# ADC.net
KiCad netlist of a schematic drawn in Altium Designer
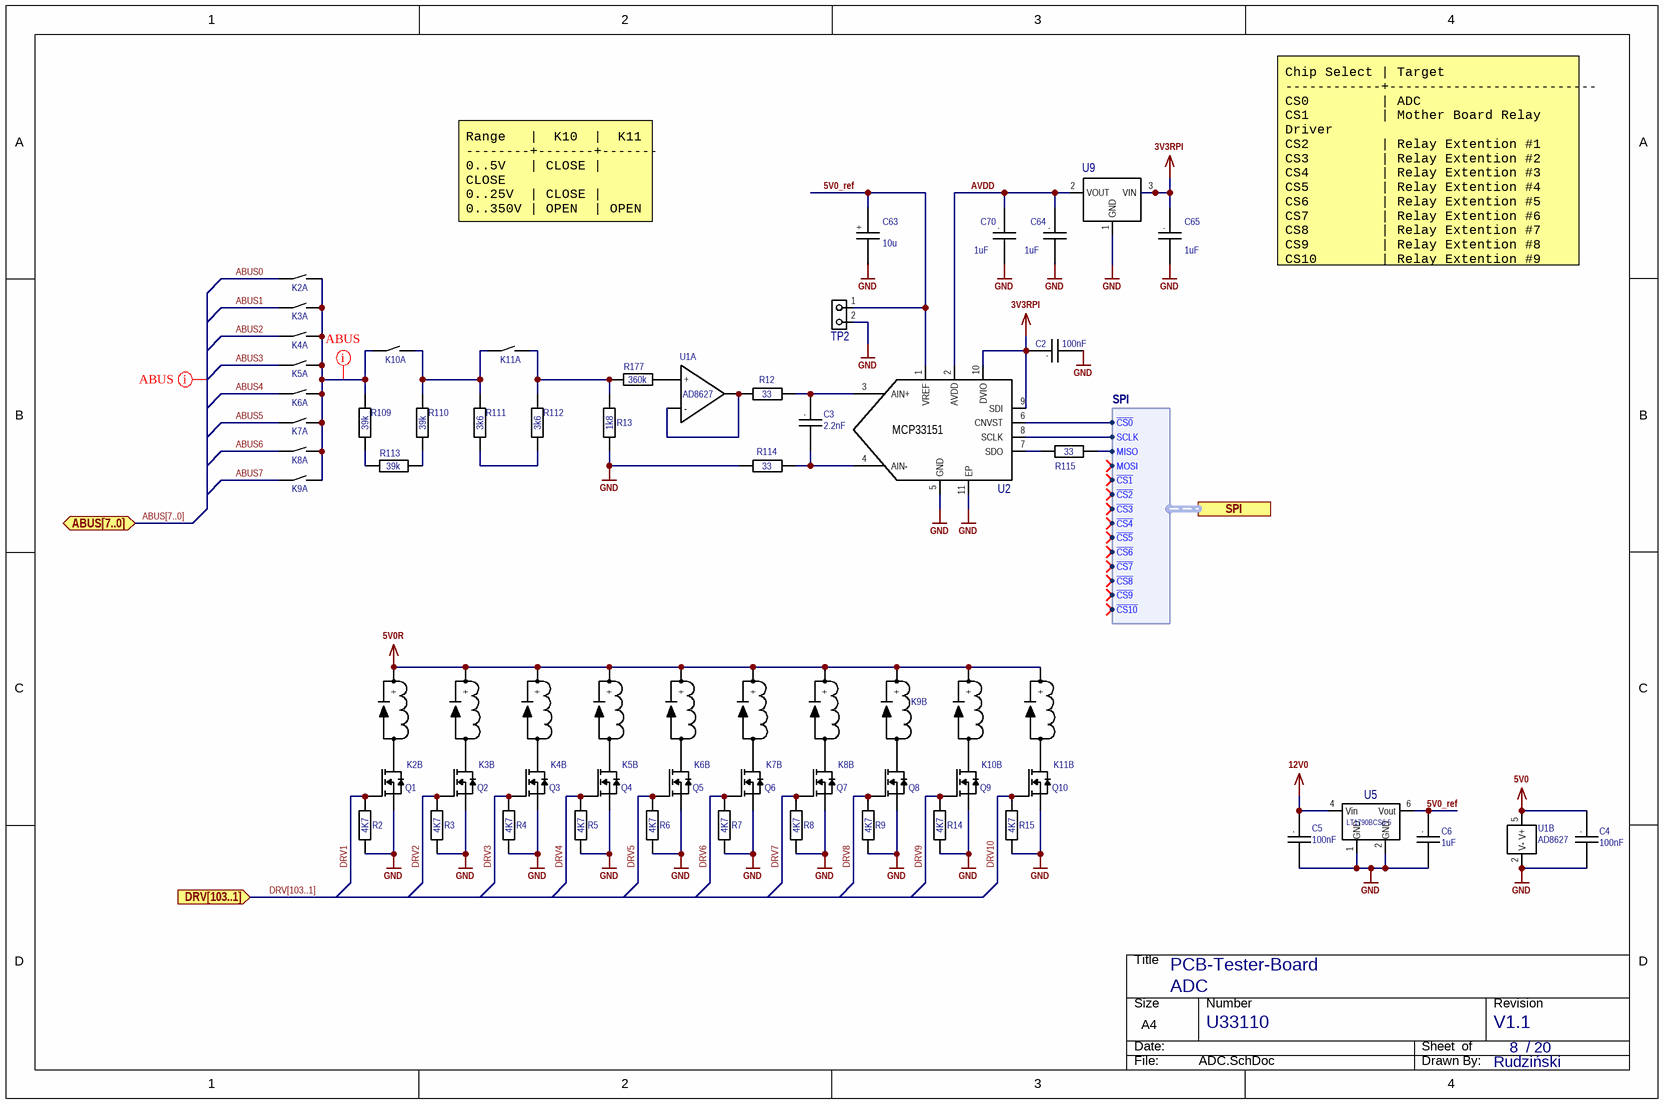
[diagram p0: ADC.SchDoc]

(export (version "E")
  (design (tool "Eeschema 10.0.6"))
  (components
    (comp (ref "C2")
      (value "100nF")
      (footprint "C0402 Reflow")
      (description "CAP CER 0.1UF 25V X7R 0402")
      (fields
        (field (name "TOLERANCE") "±5%")
        (field (name "02. DISTRIBUTOR PART NUMBER") "311-2077-6-ND")
        (field (name "13. CREATED DATE/NAME") "AUG2018/Hören")
      )
      (libsource (lib "chickenfood") (part "C"))
    )
    (comp (ref "C3")
      (value "2.2nF")
      (footprint "C0603 Reflow")
      (description "CAP CER 2200PF 50V X7R 0402")
      (fields
        (field (name "TOLERANCE") "±5%")
        (field (name "02. DISTRIBUTOR PART NUMBER") "1276-1532-6-ND")
        (field (name "13. CREATED DATE/NAME") "AUG2018/Hören")
      )
      (libsource (lib "chickenfood") (part "C"))
    )
    (comp (ref "C4")
      (value "100nF")
      (footprint "C0402 Reflow")
      (description "CAP CER 0.1UF 25V X7R 0402")
      (fields
        (field (name "TOLERANCE") "±5%")
        (field (name "02. DISTRIBUTOR PART NUMBER") "311-2077-6-ND")
        (field (name "13. CREATED DATE/NAME") "AUG2018/Hören")
      )
      (libsource (lib "chickenfood") (part "C"))
    )
    (comp (ref "C5")
      (value "100nF")
      (footprint "C0402 Reflow")
      (description "CAP CER 0.1UF 25V X7R 0402")
      (fields
        (field (name "TOLERANCE") "±5%")
        (field (name "02. DISTRIBUTOR PART NUMBER") "311-2077-6-ND")
        (field (name "13. CREATED DATE/NAME") "AUG2018/Hören")
      )
      (libsource (lib "chickenfood") (part "C"))
    )
    (comp (ref "C6")
      (value "1uF")
      (footprint "C0402 Reflow")
      (description "CAP CER 1UF 6.3V X7R 0402")
      (fields
        (field (name "TOLERANCE") "±10%")
        (field (name "02. DISTRIBUTOR PART NUMBER") "490-13339-6-ND")
        (field (name "13. CREATED DATE/NAME") "AUG2018/Hören")
      )
      (libsource (lib "chickenfood") (part "C"))
    )
    (comp (ref "C63")
      (value "10u")
      (footprint "CAP_TAN_B")
      (description "CAP TANT 10UF 20% 16V 1411")
      (fields
        (field (name "02. DISTRIBUTOR PART NUMBER") "718-2344-1-ND")
        (field (name "07. MANUFACTURER  PART NUMBER") "TMCHB1C106MTRF")
      )
      (libsource (lib "PCB-Tester-Board-V1") (part "C+_TAN"))
    )
    (comp (ref "C64")
      (value "1uF")
      (footprint "C0402 Reflow")
      (description "CAP CER 1UF 6.3V X7R 0402")
      (fields
        (field (name "TOLERANCE") "±10%")
        (field (name "02. DISTRIBUTOR PART NUMBER") "490-13339-6-ND")
        (field (name "13. CREATED DATE/NAME") "AUG2018/Hören")
      )
      (libsource (lib "chickenfood") (part "C"))
    )
    (comp (ref "C65")
      (value "1uF")
      (footprint "C0402 Reflow")
      (description "CAP CER 1UF 6.3V X7R 0402")
      (fields
        (field (name "TOLERANCE") "±10%")
        (field (name "02. DISTRIBUTOR PART NUMBER") "490-13339-6-ND")
        (field (name "13. CREATED DATE/NAME") "AUG2018/Hören")
      )
      (libsource (lib "chickenfood") (part "C"))
    )
    (comp (ref "C70")
      (value "1uF")
      (footprint "C0402 Reflow")
      (description "CAP CER 1UF 6.3V X7R 0402")
      (fields
        (field (name "TOLERANCE") "±10%")
        (field (name "02. DISTRIBUTOR PART NUMBER") "490-13339-6-ND")
        (field (name "13. CREATED DATE/NAME") "AUG2018/Hören")
      )
      (libsource (lib "chickenfood") (part "C"))
    )
    (comp (ref "K2")
      (value "K")
      (footprint "118-1A")
      (description "5V Signal Relais, Normal Open")
      (fields
        (field (name "02. DISTRIBUTOR PART NUMBER") "118-1-A-5/2D")
        (field (name "13. CREATED DATE/NAME") "20.12.17 S. Kaiser")
      )
      (libsource (lib "") (part "118-1-A-5/2D_1"))
    )
    (comp (ref "K3")
      (value "K")
      (footprint "118-1A")
      (description "5V Signal Relais, Normal Open")
      (fields
        (field (name "02. DISTRIBUTOR PART NUMBER") "118-1-A-5/2D")
        (field (name "13. CREATED DATE/NAME") "20.12.17 S. Kaiser")
      )
      (libsource (lib "") (part "118-1-A-5/2D_1"))
    )
    (comp (ref "K4")
      (value "K")
      (footprint "118-1A")
      (description "5V Signal Relais, Normal Open")
      (fields
        (field (name "02. DISTRIBUTOR PART NUMBER") "118-1-A-5/2D")
        (field (name "13. CREATED DATE/NAME") "20.12.17 S. Kaiser")
      )
      (libsource (lib "") (part "118-1-A-5/2D_1"))
    )
    (comp (ref "K5")
      (value "K")
      (footprint "118-1A")
      (description "5V Signal Relais, Normal Open")
      (fields
        (field (name "02. DISTRIBUTOR PART NUMBER") "118-1-A-5/2D")
        (field (name "13. CREATED DATE/NAME") "20.12.17 S. Kaiser")
      )
      (libsource (lib "") (part "118-1-A-5/2D_1"))
    )
    (comp (ref "K6")
      (value "K")
      (footprint "118-1A")
      (description "5V Signal Relais, Normal Open")
      (fields
        (field (name "02. DISTRIBUTOR PART NUMBER") "118-1-A-5/2D")
        (field (name "13. CREATED DATE/NAME") "20.12.17 S. Kaiser")
      )
      (libsource (lib "") (part "118-1-A-5/2D_1"))
    )
    (comp (ref "K7")
      (value "K")
      (footprint "118-1A")
      (description "5V Signal Relais, Normal Open")
      (fields
        (field (name "02. DISTRIBUTOR PART NUMBER") "118-1-A-5/2D")
        (field (name "13. CREATED DATE/NAME") "20.12.17 S. Kaiser")
      )
      (libsource (lib "chickenfood") (part "118-1-A-5/2D"))
    )
    (comp (ref "K8")
      (value "K")
      (footprint "118-1A")
      (description "5V Signal Relais, Normal Open")
      (fields
        (field (name "02. DISTRIBUTOR PART NUMBER") "118-1-A-5/2D")
        (field (name "13. CREATED DATE/NAME") "20.12.17 S. Kaiser")
      )
      (libsource (lib "chickenfood") (part "118-1-A-5/2D"))
    )
    (comp (ref "K9")
      (value "K")
      (footprint "118-1A")
      (description "5V Signal Relais, Normal Open")
      (fields
        (field (name "02. DISTRIBUTOR PART NUMBER") "118-1-A-5/2D")
        (field (name "13. CREATED DATE/NAME") "20.12.17 S. Kaiser")
      )
      (libsource (lib "") (part "118-1-A-5/2D_1"))
    )
    (comp (ref "K10")
      (value "K")
      (footprint "118-1A")
      (description "5V Signal Relais, Normal Open")
      (fields
        (field (name "02. DISTRIBUTOR PART NUMBER") "118-1-A-5/2D")
        (field (name "13. CREATED DATE/NAME") "20.12.17 S. Kaiser")
      )
      (libsource (lib "chickenfood") (part "118-1-A-5/2D"))
    )
    (comp (ref "K11")
      (value "K")
      (footprint "118-1A")
      (description "5V Signal Relais, Normal Open")
      (fields
        (field (name "02. DISTRIBUTOR PART NUMBER") "118-1-A-5/2D")
        (field (name "13. CREATED DATE/NAME") "20.12.17 S. Kaiser")
      )
      (libsource (lib "") (part "118-1-A-5/2D_1"))
    )
    (comp (ref "Q1")
      (value "Q")
      (footprint "SOT23-3")
      (description "MOSFET N-CH 25V 680MA SOT-23")
      (fields
        (field (name "02. DISTRIBUTOR PART NUMBER") "FDV303NDKR-ND")
        (field (name "07. MANUFACTURER  PART NUMBER") "FDV303N")
        (field (name "13. CREATED DATE/NAME") "AUG 2018 / Hören")
      )
      (libsource (lib "SCT8-Board1") (part "FDV303N"))
    )
    (comp (ref "Q2")
      (value "Q")
      (footprint "SOT23-3")
      (description "MOSFET N-CH 25V 680MA SOT-23")
      (fields
        (field (name "02. DISTRIBUTOR PART NUMBER") "FDV303NDKR-ND")
        (field (name "07. MANUFACTURER  PART NUMBER") "FDV303N")
        (field (name "13. CREATED DATE/NAME") "AUG 2018 / Hören")
      )
      (libsource (lib "SCT8-Board1") (part "FDV303N"))
    )
    (comp (ref "Q3")
      (value "Q")
      (footprint "SOT23-3")
      (description "MOSFET N-CH 25V 680MA SOT-23")
      (fields
        (field (name "02. DISTRIBUTOR PART NUMBER") "FDV303NDKR-ND")
        (field (name "07. MANUFACTURER  PART NUMBER") "FDV303N")
        (field (name "13. CREATED DATE/NAME") "AUG 2018 / Hören")
      )
      (libsource (lib "SCT8-Board1") (part "FDV303N"))
    )
    (comp (ref "Q4")
      (value "Q")
      (footprint "SOT23-3")
      (description "MOSFET N-CH 25V 680MA SOT-23")
      (fields
        (field (name "02. DISTRIBUTOR PART NUMBER") "FDV303NDKR-ND")
        (field (name "07. MANUFACTURER  PART NUMBER") "FDV303N")
        (field (name "13. CREATED DATE/NAME") "AUG 2018 / Hören")
      )
      (libsource (lib "SCT8-Board1") (part "FDV303N"))
    )
    (comp (ref "Q5")
      (value "Q")
      (footprint "SOT23-3")
      (description "MOSFET N-CH 25V 680MA SOT-23")
      (fields
        (field (name "02. DISTRIBUTOR PART NUMBER") "FDV303NDKR-ND")
        (field (name "07. MANUFACTURER  PART NUMBER") "FDV303N")
        (field (name "13. CREATED DATE/NAME") "AUG 2018 / Hören")
      )
      (libsource (lib "SCT8-Board1") (part "FDV303N"))
    )
    (comp (ref "Q6")
      (value "Q")
      (footprint "SOT23-3")
      (description "MOSFET N-CH 25V 680MA SOT-23")
      (fields
        (field (name "02. DISTRIBUTOR PART NUMBER") "FDV303NDKR-ND")
        (field (name "07. MANUFACTURER  PART NUMBER") "FDV303N")
        (field (name "13. CREATED DATE/NAME") "AUG 2018 / Hören")
      )
      (libsource (lib "SCT8-Board1") (part "FDV303N"))
    )
    (comp (ref "Q7")
      (value "Q")
      (footprint "SOT23-3")
      (description "MOSFET N-CH 25V 680MA SOT-23")
      (fields
        (field (name "02. DISTRIBUTOR PART NUMBER") "FDV303NDKR-ND")
        (field (name "07. MANUFACTURER  PART NUMBER") "FDV303N")
        (field (name "13. CREATED DATE/NAME") "AUG 2018 / Hören")
      )
      (libsource (lib "SCT8-Board1") (part "FDV303N"))
    )
    (comp (ref "Q8")
      (value "Q")
      (footprint "SOT23-3")
      (description "MOSFET N-CH 25V 680MA SOT-23")
      (fields
        (field (name "02. DISTRIBUTOR PART NUMBER") "FDV303NDKR-ND")
        (field (name "07. MANUFACTURER  PART NUMBER") "FDV303N")
        (field (name "13. CREATED DATE/NAME") "AUG 2018 / Hören")
      )
      (libsource (lib "SCT8-Board1") (part "FDV303N"))
    )
    (comp (ref "Q9")
      (value "Q")
      (footprint "SOT23-3")
      (description "MOSFET N-CH 25V 680MA SOT-23")
      (fields
        (field (name "02. DISTRIBUTOR PART NUMBER") "FDV303NDKR-ND")
        (field (name "07. MANUFACTURER  PART NUMBER") "FDV303N")
        (field (name "13. CREATED DATE/NAME") "AUG 2018 / Hören")
      )
      (libsource (lib "SCT8-Board1") (part "FDV303N"))
    )
    (comp (ref "Q10")
      (value "Q")
      (footprint "SOT23-3")
      (description "MOSFET N-CH 25V 680MA SOT-23")
      (fields
        (field (name "02. DISTRIBUTOR PART NUMBER") "FDV303NDKR-ND")
        (field (name "07. MANUFACTURER  PART NUMBER") "FDV303N")
        (field (name "13. CREATED DATE/NAME") "AUG 2018 / Hören")
      )
      (libsource (lib "SCT8-Board1") (part "FDV303N"))
    )
    (comp (ref "R2")
      (value "4K7")
      (footprint "R0603 Reflow")
      (description "RES SMD 4.7K OHM 1% 1/10W 0603")
      (fields
        (field (name "TOLERANCE") "±1%")
        (field (name "02. DISTRIBUTOR PART NUMBER") "311-4.70KHRCT-ND")
        (field (name "13. CREATED DATE/NAME") "AUG2018/Hören")
      )
      (libsource (lib "chickenfood") (part "R"))
    )
    (comp (ref "R3")
      (value "4K7")
      (footprint "R0603 Reflow")
      (description "RES SMD 4.7K OHM 1% 1/10W 0603")
      (fields
        (field (name "TOLERANCE") "±1%")
        (field (name "02. DISTRIBUTOR PART NUMBER") "311-4.70KHRCT-ND")
        (field (name "13. CREATED DATE/NAME") "AUG2018/Hören")
      )
      (libsource (lib "chickenfood") (part "R"))
    )
    (comp (ref "R4")
      (value "4K7")
      (footprint "R0603 Reflow")
      (description "RES SMD 4.7K OHM 1% 1/10W 0603")
      (fields
        (field (name "TOLERANCE") "±1%")
        (field (name "02. DISTRIBUTOR PART NUMBER") "311-4.70KHRCT-ND")
        (field (name "13. CREATED DATE/NAME") "AUG2018/Hören")
      )
      (libsource (lib "chickenfood") (part "R"))
    )
    (comp (ref "R5")
      (value "4K7")
      (footprint "R0603 Reflow")
      (description "RES SMD 4.7K OHM 1% 1/10W 0603")
      (fields
        (field (name "TOLERANCE") "±1%")
        (field (name "02. DISTRIBUTOR PART NUMBER") "311-4.70KHRCT-ND")
        (field (name "13. CREATED DATE/NAME") "AUG2018/Hören")
      )
      (libsource (lib "chickenfood") (part "R"))
    )
    (comp (ref "R6")
      (value "4K7")
      (footprint "R0603 Reflow")
      (description "RES SMD 4.7K OHM 1% 1/10W 0603")
      (fields
        (field (name "TOLERANCE") "±1%")
        (field (name "02. DISTRIBUTOR PART NUMBER") "311-4.70KHRCT-ND")
        (field (name "13. CREATED DATE/NAME") "AUG2018/Hören")
      )
      (libsource (lib "chickenfood") (part "R"))
    )
    (comp (ref "R7")
      (value "4K7")
      (footprint "R0603 Reflow")
      (description "RES SMD 4.7K OHM 1% 1/10W 0603")
      (fields
        (field (name "TOLERANCE") "±1%")
        (field (name "02. DISTRIBUTOR PART NUMBER") "311-4.70KHRCT-ND")
        (field (name "13. CREATED DATE/NAME") "AUG2018/Hören")
      )
      (libsource (lib "chickenfood") (part "R"))
    )
    (comp (ref "R8")
      (value "4K7")
      (footprint "R0603 Reflow")
      (description "RES SMD 4.7K OHM 1% 1/10W 0603")
      (fields
        (field (name "TOLERANCE") "±1%")
        (field (name "02. DISTRIBUTOR PART NUMBER") "311-4.70KHRCT-ND")
        (field (name "13. CREATED DATE/NAME") "AUG2018/Hören")
      )
      (libsource (lib "chickenfood") (part "R"))
    )
    (comp (ref "R9")
      (value "4K7")
      (footprint "R0603 Reflow")
      (description "RES SMD 4.7K OHM 1% 1/10W 0603")
      (fields
        (field (name "TOLERANCE") "±1%")
        (field (name "02. DISTRIBUTOR PART NUMBER") "311-4.70KHRCT-ND")
        (field (name "13. CREATED DATE/NAME") "AUG2018/Hören")
      )
      (libsource (lib "chickenfood") (part "R"))
    )
    (comp (ref "R12")
      (value "33")
      (footprint "R0402 Reflow")
      (description "RES SMD 33 OHM 1% 1/16W 0402")
      (fields
        (field (name "TOLERANCE") "±1%")
        (field (name "02. DISTRIBUTOR PART NUMBER") "311-33.0LRDKR-ND")
        (field (name "13. CREATED DATE/NAME") "AUG2018/Hören")
      )
      (libsource (lib "") (part "R_1"))
    )
    (comp (ref "R13")
      (value "1k8")
      (footprint "R0603 Reflow")
      (description "RES SMD 1.8K OHM 1% 1/16W 0402")
      (fields
        (field (name "TOLERANCE") "±1%")
        (field (name "02. DISTRIBUTOR PART NUMBER") "311-1.80KLRCT-ND")
        (field (name "13. CREATED DATE/NAME") "AUG2018/Hören")
      )
      (libsource (lib "chickenfood") (part "R"))
    )
    (comp (ref "R14")
      (value "4K7")
      (footprint "R0603 Reflow")
      (description "RES SMD 4.7K OHM 1% 1/10W 0603")
      (fields
        (field (name "TOLERANCE") "±1%")
        (field (name "02. DISTRIBUTOR PART NUMBER") "311-4.70KHRCT-ND")
        (field (name "13. CREATED DATE/NAME") "AUG2018/Hören")
      )
      (libsource (lib "chickenfood") (part "R"))
    )
    (comp (ref "R15")
      (value "4K7")
      (footprint "R0603 Reflow")
      (description "RES SMD 4.7K OHM 1% 1/10W 0603")
      (fields
        (field (name "TOLERANCE") "±1%")
        (field (name "02. DISTRIBUTOR PART NUMBER") "311-4.70KHRCT-ND")
        (field (name "13. CREATED DATE/NAME") "AUG2018/Hören")
      )
      (libsource (lib "chickenfood") (part "R"))
    )
    (comp (ref "R109")
      (value "39k")
      (footprint "R2512 Reflow")
      (description "CRGP 2512 39K 1%")
      (fields
        (field (name "TOLERANCE") "±1%")
        (field (name "02. DISTRIBUTOR PART NUMBER") "A130740CT-ND")
        (field (name "13. CREATED DATE/NAME") "AUG2018/Hören")
      )
      (libsource (lib "") (part "R_1"))
    )
    (comp (ref "R110")
      (value "39k")
      (footprint "R2512 Reflow")
      (description "CRGP 2512 39K 1%")
      (fields
        (field (name "TOLERANCE") "±1%")
        (field (name "02. DISTRIBUTOR PART NUMBER") "A130740CT-ND")
        (field (name "13. CREATED DATE/NAME") "AUG2018/Hören")
      )
      (libsource (lib "") (part "R_1"))
    )
    (comp (ref "R111")
      (value "3k6")
      (footprint "R0603 Reflow")
      (description "RES SMD 3.6K OHM 1% 1/10W 0603")
      (fields
        (field (name "TOLERANCE") "±1%")
        (field (name "02. DISTRIBUTOR PART NUMBER") "311-3.60KHRCT-ND")
        (field (name "13. CREATED DATE/NAME") "AUG2018/Hören")
      )
      (libsource (lib "") (part "R_1"))
    )
    (comp (ref "R112")
      (value "3k6")
      (footprint "R0603 Reflow")
      (description "RES SMD 3.6K OHM 1% 1/10W 0603")
      (fields
        (field (name "TOLERANCE") "±1%")
        (field (name "02. DISTRIBUTOR PART NUMBER") "311-3.60KHRCT-ND")
        (field (name "13. CREATED DATE/NAME") "AUG2018/Hören")
      )
      (libsource (lib "") (part "R_1"))
    )
    (comp (ref "R113")
      (value "39k")
      (footprint "R2512 Reflow")
      (description "CRGP 2512 39K 1%")
      (fields
        (field (name "TOLERANCE") "±1%")
        (field (name "02. DISTRIBUTOR PART NUMBER") "A130740CT-ND")
        (field (name "13. CREATED DATE/NAME") "AUG2018/Hören")
      )
      (libsource (lib "PCB-Tester-Board-V1") (part "R"))
    )
    (comp (ref "R114")
      (value "33")
      (footprint "R0402 Reflow")
      (description "RES SMD 33 OHM 1% 1/16W 0402")
      (fields
        (field (name "TOLERANCE") "±1%")
        (field (name "02. DISTRIBUTOR PART NUMBER") "311-33.0LRDKR-ND")
        (field (name "13. CREATED DATE/NAME") "AUG2018/Hören")
      )
      (libsource (lib "") (part "R_1"))
    )
    (comp (ref "R115")
      (value "33")
      (footprint "R0402 Reflow")
      (description "RES SMD 33 OHM 1% 1/16W 0402")
      (fields
        (field (name "TOLERANCE") "±1%")
        (field (name "02. DISTRIBUTOR PART NUMBER") "311-33.0LRDKR-ND")
        (field (name "13. CREATED DATE/NAME") "AUG2018/Hören")
      )
      (libsource (lib "PCB-Tester-Board-V1") (part "R_19"))
    )
    (comp (ref "R177")
      (value "360k")
      (footprint "R1206 Reflow")
      (description "RES SMD 360K OHM 1% 1/4W 1206")
      (fields
        (field (name "TOLERANCE") "±1%")
        (field (name "02. DISTRIBUTOR PART NUMBER") "311-360KFRCT-ND")
        (field (name "13. CREATED DATE/NAME") "AUG2018/Hören")
      )
      (libsource (lib "") (part "R_1"))
    )
    (comp (ref "TP2")
      (value "TP")
      (footprint "DualTestpoint 100mils")
      (description "Dual testpoint, pitch 2.54mm")
      (fields
        (field (name "02. DISTRIBUTOR PART NUMBER") "HMTSW-103-07-G-S-240")
        (field (name "13. CREATED DATE/NAME") "AUG2018/Hören")
      )
      (libsource (lib "PCB-Tester-Board-V1") (part "DualTestpoint 100mils"))
    )
    (comp (ref "U1")
      (value "U")
      (footprint "SC70-5")
      (description "IC OPAMP JFET 5MHZ RRO SC70-5")
      (fields
        (field (name "02. DISTRIBUTOR PART NUMBER") "AD8627AKSZ-R2DKR-ND")
        (field (name "07. MANUFACTURER  PART NUMBER") "AD8627AKSZ-R2")
        (field (name "PART") "AD8627")
        (field (name "13. CREATED DATE/NAME") "AUG 2018 / Hören")
      )
      (libsource (lib "PCB-Tester-Board") (part "AD8627"))
    )
    (comp (ref "U2")
      (value "U")
      (footprint "TDFN10EP")
      (description "14-BIT 1 MSPS SGL CH SGL-ENDED S")
      (fields
        (field (name "02. DISTRIBUTOR PART NUMBER") "MCP33151-10T-E/MNDKR-ND")
        (field (name "07. MANUFACTURER  PART NUMBER") "MCP33151-10T-E/MN")
        (field (name "NICNAME") "MCP33151")
        (field (name "13. CREATED DATE/NAME") "AUG 2018 / Hören")
      )
      (libsource (lib "tom") (part "MCP33151-10T-E/MN"))
    )
    (comp (ref "U5")
      (value "U")
      (footprint "TSOT23-6(S6)")
      (description "IC VREF SERIES 5V, 0.1% TSOT-23-6")
      (fields
        (field (name "02. DISTRIBUTOR PART NUMBER") "LT1790BCS6-5#TRMPBFDKR-ND")
        (field (name "07. MANUFACTURER  PART NUMBER") "LT1790BCS6-5#TRMPBF")
        (field (name "NICNAME") "LT1790BCS6-5")
        (field (name "13. CREATED DATE/NAME") "AUG 2018 / Hören")
      )
      (libsource (lib "tom") (part "LT1790BCS6-5"))
    )
    (comp (ref "U9")
      (value "U")
      (footprint "SOT23-3")
      (description "IC REG LINEAR 1.8V 250MA SOT23-3")
      (fields
        (field (name "02. DISTRIBUTOR PART NUMBER") "AP2138N-1.8TRG1DICT-ND")
        (field (name "07. MANUFACTURER  PART NUMBER") "AP2138N-1.8TRG1")
      )
      (libsource (lib "PCB-Tester-Board-V1") (part "AP2138N"))
    )
  )
  (nets
    (net (code "95") (name "/5V0_ref") (class "Default")
      (node (ref "C6") (pin "1") (pinfunction "1_1") (pintype "passive"))
      (node (ref "C63") (pin "1") (pinfunction "1_1") (pintype "passive"))
      (node (ref "TP2") (pin "1") (pinfunction "1_1") (pintype "passive"))
      (node (ref "U2") (pin "1") (pinfunction "VREF_1") (pintype "passive"))
      (node (ref "U5") (pin "6") (pinfunction "Vout_6") (pintype "passive"))
    )
    (net (code "96") (name "/ABUS0") (class "Default")
      (node (ref "K2") (pin "4") (pinfunction "CB_4") (pintype "passive"))
    )
    (net (code "97") (name "/ABUS1") (class "Default")
      (node (ref "K3") (pin "4") (pinfunction "CB_4") (pintype "passive"))
    )
    (net (code "98") (name "/ABUS2") (class "Default")
      (node (ref "K4") (pin "4") (pinfunction "CB_4") (pintype "passive"))
    )
    (net (code "99") (name "/ABUS3") (class "Default")
      (node (ref "K5") (pin "4") (pinfunction "CB_4") (pintype "passive"))
    )
    (net (code "100") (name "/ABUS4") (class "Default")
      (node (ref "K6") (pin "4") (pinfunction "CB_4") (pintype "passive"))
    )
    (net (code "101") (name "/ABUS5") (class "Default")
      (node (ref "K7") (pin "4") (pinfunction "CB_4") (pintype "passive"))
    )
    (net (code "102") (name "/ABUS6") (class "Default")
      (node (ref "K8") (pin "4") (pinfunction "CB_4") (pintype "passive"))
    )
    (net (code "103") (name "/ABUS7") (class "Default")
      (node (ref "K9") (pin "4") (pinfunction "CB_4") (pintype "passive"))
    )
    (net (code "105") (name "/AVDD") (class "Default")
      (node (ref "C64") (pin "1") (pinfunction "1_1") (pintype "passive"))
      (node (ref "C70") (pin "1") (pinfunction "1_1") (pintype "passive"))
      (node (ref "U2") (pin "2") (pinfunction "AVDD_2") (pintype "passive"))
      (node (ref "U9") (pin "2") (pinfunction "VOUT_2") (pintype "passive"))
    )
    (net (code "106") (name "/DRV1") (class "Default")
      (node (ref "Q1") (pin "1") (pinfunction "G_1") (pintype "passive"))
      (node (ref "R2") (pin "2") (pinfunction "2_2") (pintype "passive"))
    )
    (net (code "107") (name "/DRV2") (class "Default")
      (node (ref "Q2") (pin "1") (pinfunction "G_1") (pintype "passive"))
      (node (ref "R3") (pin "2") (pinfunction "2_2") (pintype "passive"))
    )
    (net (code "108") (name "/DRV3") (class "Default")
      (node (ref "Q3") (pin "1") (pinfunction "G_1") (pintype "passive"))
      (node (ref "R4") (pin "2") (pinfunction "2_2") (pintype "passive"))
    )
    (net (code "109") (name "/DRV4") (class "Default")
      (node (ref "Q4") (pin "1") (pinfunction "G_1") (pintype "passive"))
      (node (ref "R5") (pin "2") (pinfunction "2_2") (pintype "passive"))
    )
    (net (code "110") (name "/DRV5") (class "Default")
      (node (ref "Q5") (pin "1") (pinfunction "G_1") (pintype "passive"))
      (node (ref "R6") (pin "2") (pinfunction "2_2") (pintype "passive"))
    )
    (net (code "111") (name "/DRV6") (class "Default")
      (node (ref "Q6") (pin "1") (pinfunction "G_1") (pintype "passive"))
      (node (ref "R7") (pin "2") (pinfunction "2_2") (pintype "passive"))
    )
    (net (code "112") (name "/DRV7") (class "Default")
      (node (ref "Q7") (pin "1") (pinfunction "G_1") (pintype "passive"))
      (node (ref "R8") (pin "2") (pinfunction "2_2") (pintype "passive"))
    )
    (net (code "113") (name "/DRV8") (class "Default")
      (node (ref "Q8") (pin "1") (pinfunction "G_1") (pintype "passive"))
      (node (ref "R9") (pin "2") (pinfunction "2_2") (pintype "passive"))
    )
    (net (code "114") (name "/DRV9") (class "Default")
      (node (ref "Q9") (pin "1") (pinfunction "G_1") (pintype "passive"))
      (node (ref "R14") (pin "2") (pinfunction "2_2") (pintype "passive"))
    )
    (net (code "115") (name "/DRV10") (class "Default")
      (node (ref "Q10") (pin "1") (pinfunction "G_1") (pintype "passive"))
      (node (ref "R15") (pin "2") (pinfunction "2_2") (pintype "passive"))
    )
    (net (code "117") (name "/MISO") (class "Default")
      (node (ref "R115") (pin "2") (pinfunction "2_2") (pintype "passive"))
    )
    (net (code "118") (name "/SCLK") (class "Default")
      (node (ref "U2") (pin "8") (pinfunction "SCLK_8") (pintype "passive"))
    )
    (net (code "120") (name "/~{CS0}") (class "Default")
      (node (ref "U2") (pin "6") (pinfunction "CNVST_6") (pintype "passive"))
    )
    (net (code "121") (name "3V3RPI") (class "Default")
      (node (ref "C2") (pin "1") (pinfunction "1_1") (pintype "passive"))
      (node (ref "C65") (pin "1") (pinfunction "1_1") (pintype "passive"))
      (node (ref "U2") (pin "10") (pinfunction "DVIO_10") (pintype "passive"))
      (node (ref "U2") (pin "9") (pinfunction "SDI_9") (pintype "passive"))
      (node (ref "U9") (pin "3") (pinfunction "VIN_3") (pintype "passive"))
    )
    (net (code "122") (name "5V0") (class "Default")
      (node (ref "C4") (pin "1") (pinfunction "1_1") (pintype "passive"))
      (node (ref "U1") (pin "5") (pinfunction "V+_5") (pintype "passive"))
    )
    (net (code "123") (name "5V0R") (class "Default")
      (node (ref "K10") (pin "1") (pinfunction "+_1") (pintype "passive"))
      (node (ref "K11") (pin "1") (pinfunction "+_1") (pintype "passive"))
      (node (ref "K2") (pin "1") (pinfunction "+_1") (pintype "passive"))
      (node (ref "K3") (pin "1") (pinfunction "+_1") (pintype "passive"))
      (node (ref "K4") (pin "1") (pinfunction "+_1") (pintype "passive"))
      (node (ref "K5") (pin "1") (pinfunction "+_1") (pintype "passive"))
      (node (ref "K6") (pin "1") (pinfunction "+_1") (pintype "passive"))
      (node (ref "K7") (pin "1") (pinfunction "+_1") (pintype "passive"))
      (node (ref "K8") (pin "1") (pinfunction "+_1") (pintype "passive"))
      (node (ref "K9") (pin "1") (pinfunction "+_1") (pintype "passive"))
    )
    (net (code "124") (name "12V0") (class "Default")
      (node (ref "C5") (pin "1") (pinfunction "1_1") (pintype "passive"))
      (node (ref "U5") (pin "4") (pinfunction "Vin_4") (pintype "passive"))
    )
    (net (code "125") (name "GND") (class "Default")
      (node (ref "C2") (pin "2") (pinfunction "2_2") (pintype "passive"))
      (node (ref "C4") (pin "2") (pinfunction "2_2") (pintype "passive"))
      (node (ref "C5") (pin "2") (pinfunction "2_2") (pintype "passive"))
      (node (ref "C6") (pin "2") (pinfunction "2_2") (pintype "passive"))
      (node (ref "C63") (pin "2") (pinfunction "2_2") (pintype "passive"))
      (node (ref "C64") (pin "2") (pinfunction "2_2") (pintype "passive"))
      (node (ref "C65") (pin "2") (pinfunction "2_2") (pintype "passive"))
      (node (ref "C70") (pin "2") (pinfunction "2_2") (pintype "passive"))
      (node (ref "Q1") (pin "2") (pinfunction "S_2") (pintype "passive"))
      (node (ref "Q10") (pin "2") (pinfunction "S_2") (pintype "passive"))
      (node (ref "Q2") (pin "2") (pinfunction "S_2") (pintype "passive"))
      (node (ref "Q3") (pin "2") (pinfunction "S_2") (pintype "passive"))
      (node (ref "Q4") (pin "2") (pinfunction "S_2") (pintype "passive"))
      (node (ref "Q5") (pin "2") (pinfunction "S_2") (pintype "passive"))
      (node (ref "Q6") (pin "2") (pinfunction "S_2") (pintype "passive"))
      (node (ref "Q7") (pin "2") (pinfunction "S_2") (pintype "passive"))
      (node (ref "Q8") (pin "2") (pinfunction "S_2") (pintype "passive"))
      (node (ref "Q9") (pin "2") (pinfunction "S_2") (pintype "passive"))
      (node (ref "R114") (pin "2") (pinfunction "2_2") (pintype "passive"))
      (node (ref "R13") (pin "1") (pinfunction "1_1") (pintype "passive"))
      (node (ref "R14") (pin "1") (pinfunction "1_1") (pintype "passive"))
      (node (ref "R15") (pin "1") (pinfunction "1_1") (pintype "passive"))
      (node (ref "R2") (pin "1") (pinfunction "1_1") (pintype "passive"))
      (node (ref "R3") (pin "1") (pinfunction "1_1") (pintype "passive"))
      (node (ref "R4") (pin "1") (pinfunction "1_1") (pintype "passive"))
      (node (ref "R5") (pin "1") (pinfunction "1_1") (pintype "passive"))
      (node (ref "R6") (pin "1") (pinfunction "1_1") (pintype "passive"))
      (node (ref "R7") (pin "1") (pinfunction "1_1") (pintype "passive"))
      (node (ref "R8") (pin "1") (pinfunction "1_1") (pintype "passive"))
      (node (ref "R9") (pin "1") (pinfunction "1_1") (pintype "passive"))
      (node (ref "TP2") (pin "2") (pinfunction "2_2") (pintype "passive"))
      (node (ref "U1") (pin "2") (pinfunction "V-_2") (pintype "passive"))
      (node (ref "U2") (pin "11") (pinfunction "EP_11") (pintype "passive"))
      (node (ref "U2") (pin "5") (pinfunction "GND_5") (pintype "passive"))
      (node (ref "U5") (pin "1") (pinfunction "GND_1") (pintype "passive"))
      (node (ref "U5") (pin "2") (pinfunction "GND_2") (pintype "passive"))
      (node (ref "U9") (pin "1") (pinfunction "GND_1") (pintype "passive"))
    )
    (net (code "126") (name "Net-(K2B--)") (class "Default")
      (node (ref "K2") (pin "2") (pinfunction "-_2") (pintype "passive"))
      (node (ref "Q1") (pin "3") (pinfunction "D_3") (pintype "passive"))
    )
    (net (code "127") (name "Net-(K3B--)") (class "Default")
      (node (ref "K3") (pin "2") (pinfunction "-_2") (pintype "passive"))
      (node (ref "Q2") (pin "3") (pinfunction "D_3") (pintype "passive"))
    )
    (net (code "128") (name "Net-(K4B--)") (class "Default")
      (node (ref "K4") (pin "2") (pinfunction "-_2") (pintype "passive"))
      (node (ref "Q3") (pin "3") (pinfunction "D_3") (pintype "passive"))
    )
    (net (code "129") (name "Net-(K5B--)") (class "Default")
      (node (ref "K5") (pin "2") (pinfunction "-_2") (pintype "passive"))
      (node (ref "Q4") (pin "3") (pinfunction "D_3") (pintype "passive"))
    )
    (net (code "130") (name "Net-(K6B--)") (class "Default")
      (node (ref "K6") (pin "2") (pinfunction "-_2") (pintype "passive"))
      (node (ref "Q5") (pin "3") (pinfunction "D_3") (pintype "passive"))
    )
    (net (code "131") (name "Net-(K7B--)") (class "Default")
      (node (ref "K7") (pin "2") (pinfunction "-_2") (pintype "passive"))
      (node (ref "Q6") (pin "3") (pinfunction "D_3") (pintype "passive"))
    )
    (net (code "132") (name "Net-(K8B--)") (class "Default")
      (node (ref "K8") (pin "2") (pinfunction "-_2") (pintype "passive"))
      (node (ref "Q7") (pin "3") (pinfunction "D_3") (pintype "passive"))
    )
    (net (code "133") (name "Net-(K9B--)") (class "Default")
      (node (ref "K9") (pin "2") (pinfunction "-_2") (pintype "passive"))
      (node (ref "Q8") (pin "3") (pinfunction "D_3") (pintype "passive"))
    )
    (net (code "134") (name "Net-(K10A-CA)") (class "Default")
      (node (ref "K10") (pin "3") (pinfunction "CA_3") (pintype "passive"))
      (node (ref "K11") (pin "4") (pinfunction "CB_4") (pintype "passive"))
      (node (ref "R110") (pin "2") (pinfunction "2_2") (pintype "passive"))
      (node (ref "R111") (pin "2") (pinfunction "2_2") (pintype "passive"))
    )
    (net (code "135") (name "Net-(K10A-CB)") (class "Default")
      (node (ref "K10") (pin "4") (pinfunction "CB_4") (pintype "passive"))
      (node (ref "K2") (pin "3") (pinfunction "CA_3") (pintype "passive"))
      (node (ref "K3") (pin "3") (pinfunction "CA_3") (pintype "passive"))
      (node (ref "K4") (pin "3") (pinfunction "CA_3") (pintype "passive"))
      (node (ref "K5") (pin "3") (pinfunction "CA_3") (pintype "passive"))
      (node (ref "K6") (pin "3") (pinfunction "CA_3") (pintype "passive"))
      (node (ref "K7") (pin "3") (pinfunction "CA_3") (pintype "passive"))
      (node (ref "K8") (pin "3") (pinfunction "CA_3") (pintype "passive"))
      (node (ref "K9") (pin "3") (pinfunction "CA_3") (pintype "passive"))
      (node (ref "R109") (pin "2") (pinfunction "2_2") (pintype "passive"))
    )
    (net (code "136") (name "Net-(K10B--)") (class "Default")
      (node (ref "K10") (pin "2") (pinfunction "-_2") (pintype "passive"))
      (node (ref "Q9") (pin "3") (pinfunction "D_3") (pintype "passive"))
    )
    (net (code "137") (name "Net-(K11A-CA)") (class "Default")
      (node (ref "K11") (pin "3") (pinfunction "CA_3") (pintype "passive"))
      (node (ref "R112") (pin "2") (pinfunction "2_2") (pintype "passive"))
      (node (ref "R13") (pin "2") (pinfunction "2_2") (pintype "passive"))
      (node (ref "R177") (pin "2") (pinfunction "2_2") (pintype "passive"))
    )
    (net (code "138") (name "Net-(K11B--)") (class "Default")
      (node (ref "K11") (pin "2") (pinfunction "-_2") (pintype "passive"))
      (node (ref "Q10") (pin "3") (pinfunction "D_3") (pintype "passive"))
    )
    (net (code "139") (name "Net-(R109-Pad1)") (class "Default")
      (node (ref "R109") (pin "1") (pinfunction "1_1") (pintype "passive"))
      (node (ref "R113") (pin "2") (pinfunction "2_2") (pintype "passive"))
    )
    (net (code "140") (name "Net-(R110-Pad1)") (class "Default")
      (node (ref "R110") (pin "1") (pinfunction "1_1") (pintype "passive"))
      (node (ref "R113") (pin "1") (pinfunction "1_1") (pintype "passive"))
    )
    (net (code "141") (name "Net-(R111-Pad1)") (class "Default")
      (node (ref "R111") (pin "1") (pinfunction "1_1") (pintype "passive"))
      (node (ref "R112") (pin "1") (pinfunction "1_1") (pintype "passive"))
    )
    (net (code "142") (name "Net-(U1A-+)") (class "Default")
      (node (ref "R177") (pin "1") (pinfunction "1_1") (pintype "passive"))
      (node (ref "U1") (pin "3") (pinfunction "+_3") (pintype "passive"))
    )
    (net (code "143") (name "Net-(U1A--)") (class "Default")
      (node (ref "R12") (pin "2") (pinfunction "2_2") (pintype "passive"))
      (node (ref "U1") (pin "1") (pinfunction "Out_1") (pintype "passive"))
      (node (ref "U1") (pin "4") (pinfunction "-_4") (pintype "passive"))
    )
    (net (code "144") (name "Net-(U2-AIN+)") (class "Default")
      (node (ref "C3") (pin "1") (pinfunction "1_1") (pintype "passive"))
      (node (ref "R12") (pin "1") (pinfunction "1_1") (pintype "passive"))
      (node (ref "U2") (pin "3") (pinfunction "AIN+_3") (pintype "passive"))
    )
    (net (code "145") (name "Net-(U2-AIN-)") (class "Default")
      (node (ref "C3") (pin "2") (pinfunction "2_2") (pintype "passive"))
      (node (ref "R114") (pin "1") (pinfunction "1_1") (pintype "passive"))
      (node (ref "U2") (pin "4") (pinfunction "AIN-_4") (pintype "passive"))
    )
    (net (code "146") (name "Net-(U2-SDO)") (class "Default")
      (node (ref "R115") (pin "1") (pinfunction "1_1") (pintype "passive"))
      (node (ref "U2") (pin "7") (pinfunction "SDO_7") (pintype "passive"))
    )
  )
)
